# design.net
KiCad netlist of a schematic drawn in Altium Designer
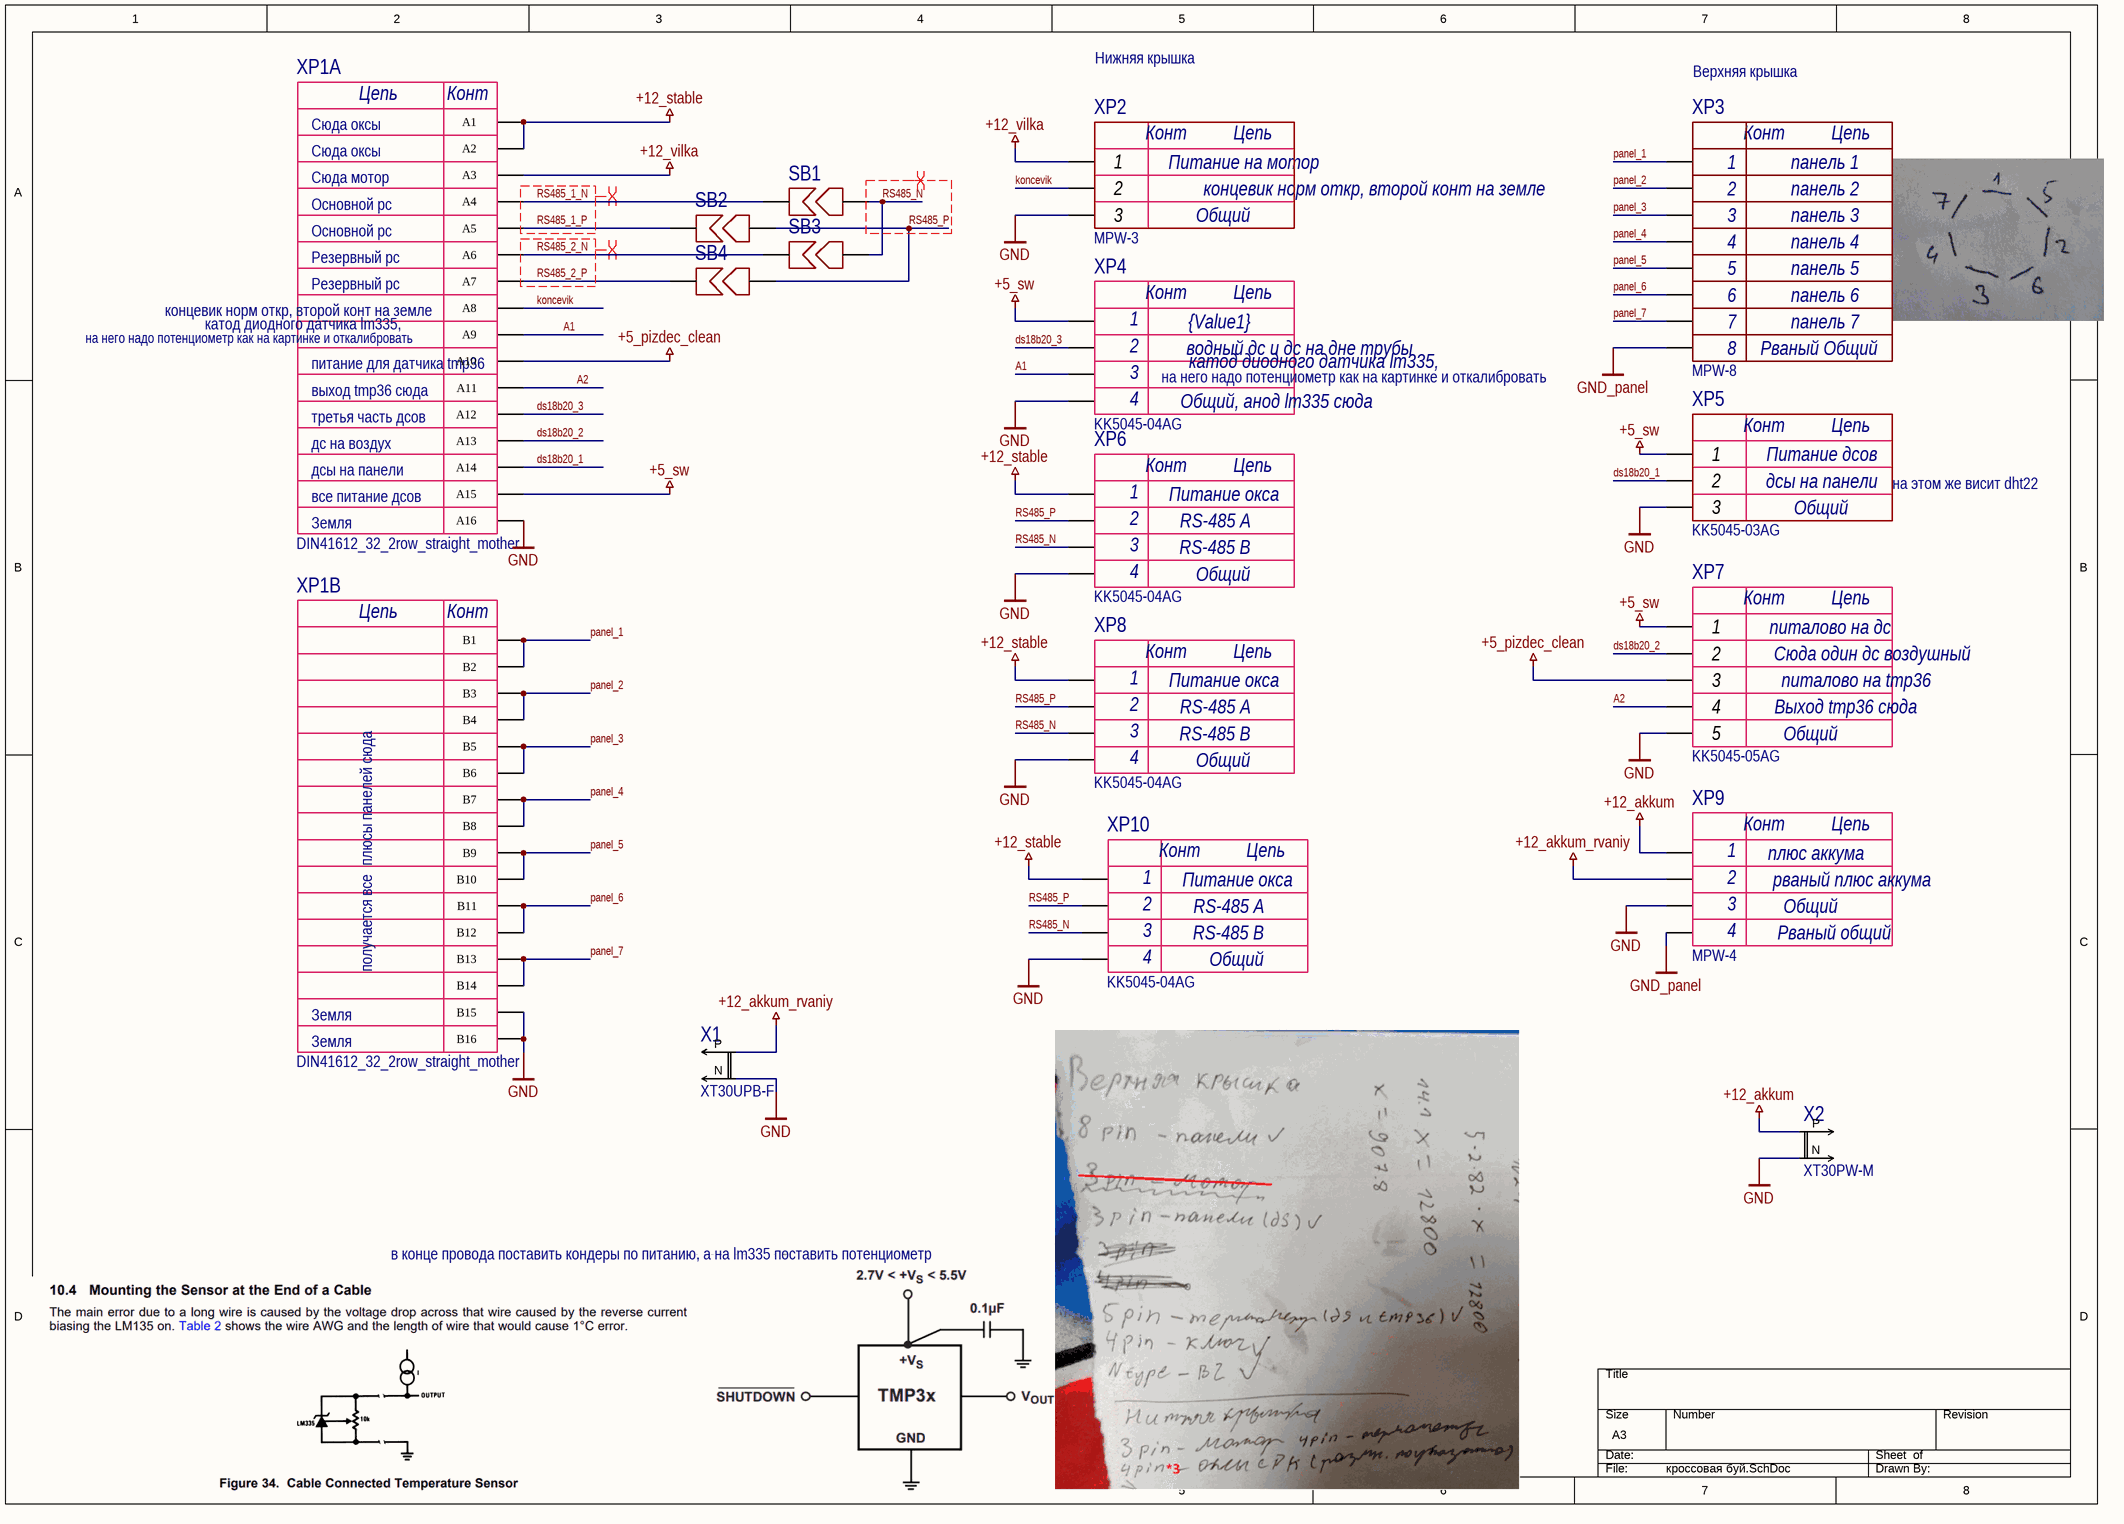
[diagram p0: кроссовая буй.SchDoc]

(export (version "E")
  (design (tool "Eeschema 10.0.6"))
  (components
    (comp (ref "SB1")
      (value "SB")
      (footprint "0805SB")
      (description "Solder bridge, мост припоя, запаиваемая перемычка, net tie, jumper")
      (libsource (lib "Hydrolib") (part "SB"))
    )
    (comp (ref "SB2")
      (value "SB")
      (footprint "0805SB")
      (description "Solder bridge, мост припоя, запаиваемая перемычка, net tie, jumper")
      (libsource (lib "Hydrolib") (part "SB"))
    )
    (comp (ref "SB3")
      (value "SB")
      (footprint "0805SB")
      (description "Solder bridge, мост припоя, запаиваемая перемычка, net tie, jumper")
      (libsource (lib "Hydrolib") (part "SB"))
    )
    (comp (ref "SB4")
      (value "SB")
      (footprint "0805SB")
      (description "Solder bridge, мост припоя, запаиваемая перемычка, net tie, jumper")
      (libsource (lib "Hydrolib") (part "SB"))
    )
    (comp (ref "X1")
      (value "XT30UPB-F")
      (footprint "XT30UPB-F")
      (description "30 А (15 продолжительно), прямая мать")
      (libsource (lib "Hydrolib") (part "Polar_Conn"))
    )
    (comp (ref "X2")
      (value "XT30PW-M")
      (footprint "XT30PW-M")
      (description "30 А (15 продолжительно), 2 контакта разъем угловой отец")
      (libsource (lib "Hydrolib") (part "Polar_Conn"))
    )
    (comp (ref "XP1")
      (value "DIN41612_32_2row_straight_mother")
      (footprint "DIN41612_32_2row_straight_mother")
      (libsource (lib "Hydrolib") (part "DIN41612_32_2row"))
    )
    (comp (ref "XP2")
      (value "MPW-3")
      (footprint "MPW-3")
      (description "MPW-3 , Вилка на плату 5.08мм прямая 3pin")
      (fields
        (field (name "VALUE3") "Общий")
        (field (name "VALUE2") "концевик норм откр, второй конт на земле")
        (field (name "VALUE1") "Питание на мотор")
      )
      (libsource (lib "Hydrolib") (part "Conn_3pin"))
    )
    (comp (ref "XP3")
      (value "MPW-8")
      (footprint "MPW-8")
      (description "MPW-8 , Вилка на плату 5.08мм прямая 8pin")
      (fields
        (field (name "VALUE1") "панель 1")
        (field (name "VALUE2") "панель 2")
        (field (name "VALUE3") "панель 3")
        (field (name "VALUE4") "панель 4")
        (field (name "VALUE5") "панель 5")
        (field (name "VALUE6") "панель 6")
        (field (name "VALUE7") "панель 7")
        (field (name "VALUE8") "Рваный Общий")
      )
      (libsource (lib "Hydrolib") (part "Conn_8pin"))
    )
    (comp (ref "XP4")
      (value "KK5045-04AG")
      (footprint "KK5045-04AG")
      (description "Разъем типа провод-плата, 2.5 мм, 4 контакта")
      (fields
        (field (name "VALUE3") "катод диодного датчика lm335,")
        (field (name "VALUE2") "водный дс и дс на дне трубы")
        (field (name "VALUE4") "Общий, анод lm335 сюда")
        (field (name "ПИТАЛОВО НА ДС") "{Value1}")
      )
      (libsource (lib "Hydrolib") (part "Conn_4pin"))
    )
    (comp (ref "XP5")
      (value "KK5045-03AG")
      (footprint "KK5045-03AG")
      (description "Разъем типа провод-плата, 2.5 мм, 3 контакта")
      (fields
        (field (name "VALUE3") "Общий")
        (field (name "VALUE2") "дсы на панели")
        (field (name "VALUE1") "Питание дсов")
      )
      (libsource (lib "Hydrolib") (part "Conn_3pin"))
    )
    (comp (ref "XP6")
      (value "KK5045-04AG")
      (footprint "KK5045-04AG")
      (description "Разъем типа провод-плата, 2.5 мм, 4 контакта")
      (fields
        (field (name "VALUE3") "RS-485 B")
        (field (name "VALUE2") "RS-485 A")
        (field (name "VALUE4") "Общий")
        (field (name "VALUE1") "Питание окса")
      )
      (libsource (lib "Hydrolib") (part "Conn_4pin"))
    )
    (comp (ref "XP7")
      (value "KK5045-05AG")
      (footprint "KK5045-05AG")
      (description "Разъем типа провод-плата, 2.5 мм, 5 контакта")
      (fields
        (field (name "VALUE1") "питалово на дс")
        (field (name "VALUE2") "Сюда один дс воздушный")
        (field (name "VALUE3") "питалово на tmp36")
        (field (name "VALUE4") "Выход tmp36 сюда")
        (field (name "VALUE5") "Общий")
      )
      (libsource (lib "Hydrolib") (part "Conn_5pin"))
    )
    (comp (ref "XP8")
      (value "KK5045-04AG")
      (footprint "KK5045-04AG")
      (description "Разъем типа провод-плата, 2.5 мм, 4 контакта")
      (fields
        (field (name "VALUE3") "RS-485 B")
        (field (name "VALUE2") "RS-485 A")
        (field (name "VALUE4") "Общий")
        (field (name "VALUE1") "Питание окса")
      )
      (libsource (lib "Hydrolib") (part "Conn_4pin"))
    )
    (comp (ref "XP9")
      (value "MPW-4")
      (footprint "MPW-4")
      (description "MPW-4 , Вилка на плату 5.08мм прямая 4pin")
      (fields
        (field (name "VALUE3") "Общий")
        (field (name "VALUE2") "рваный плюс аккума")
        (field (name "VALUE4") "Рваный общий")
        (field (name "VALUE1") "плюс аккума")
      )
      (libsource (lib "Hydrolib") (part "Conn_4pin"))
    )
    (comp (ref "XP10")
      (value "KK5045-04AG")
      (footprint "KK5045-04AG")
      (description "Разъем типа провод-плата, 2.5 мм, 4 контакта")
      (fields
        (field (name "VALUE3") "RS-485 B")
        (field (name "VALUE2") "RS-485 A")
        (field (name "VALUE4") "Общий")
        (field (name "VALUE1") "Питание окса")
      )
      (libsource (lib "Hydrolib") (part "Conn_4pin"))
    )
  )
  (nets
    (net (code "1") (name "+5_pizdec_clean") (class "Default")
      (node (ref "XP1") (pin "A10") (pinfunction "A10_A10") (pintype "passive"))
      (node (ref "XP7") (pin "3") (pinfunction "3_3") (pintype "passive"))
    )
    (net (code "2") (name "+5_sw") (class "Default")
      (node (ref "XP1") (pin "A15") (pinfunction "A15_A15") (pintype "passive"))
      (node (ref "XP4") (pin "1") (pinfunction "1_1") (pintype "passive"))
      (node (ref "XP5") (pin "1") (pinfunction "1_1") (pintype "passive"))
      (node (ref "XP7") (pin "1") (pinfunction "1_1") (pintype "passive"))
    )
    (net (code "3") (name "+12_akkum") (class "Default")
      (node (ref "X2") (pin "P") (pinfunction "P_P") (pintype "passive"))
      (node (ref "XP9") (pin "1") (pinfunction "1_1") (pintype "passive"))
    )
    (net (code "4") (name "+12_akkum_rvaniy") (class "Default")
      (node (ref "X1") (pin "P") (pinfunction "P_P") (pintype "passive"))
      (node (ref "XP9") (pin "2") (pinfunction "2_2") (pintype "passive"))
    )
    (net (code "5") (name "+12_stable") (class "Default")
      (node (ref "XP1") (pin "A1") (pinfunction "A1_A1") (pintype "passive"))
      (node (ref "XP1") (pin "A2") (pinfunction "A2_A2") (pintype "passive"))
      (node (ref "XP10") (pin "1") (pinfunction "1_1") (pintype "passive"))
      (node (ref "XP6") (pin "1") (pinfunction "1_1") (pintype "passive"))
      (node (ref "XP8") (pin "1") (pinfunction "1_1") (pintype "passive"))
    )
    (net (code "6") (name "+12_vilka") (class "Default")
      (node (ref "XP1") (pin "A3") (pinfunction "A3_A3") (pintype "passive"))
      (node (ref "XP2") (pin "1") (pinfunction "1_1") (pintype "passive"))
    )
    (net (code "7") (name "/A1") (class "Default")
      (node (ref "XP1") (pin "A9") (pinfunction "A9_A9") (pintype "passive"))
      (node (ref "XP4") (pin "3") (pinfunction "3_3") (pintype "passive"))
    )
    (net (code "8") (name "/A2") (class "Default")
      (node (ref "XP1") (pin "A11") (pinfunction "A11_A11") (pintype "passive"))
      (node (ref "XP7") (pin "4") (pinfunction "4_4") (pintype "passive"))
    )
    (net (code "9") (name "/RS485_1_N") (class "Default")
      (node (ref "SB1") (pin "1") (pinfunction "1_1") (pintype "passive"))
      (node (ref "XP1") (pin "A4") (pinfunction "A4_A4") (pintype "passive"))
    )
    (net (code "10") (name "/RS485_1_P") (class "Default")
      (node (ref "SB2") (pin "1") (pinfunction "1_1") (pintype "passive"))
      (node (ref "XP1") (pin "A5") (pinfunction "A5_A5") (pintype "passive"))
    )
    (net (code "11") (name "/RS485_2_N") (class "Default")
      (node (ref "SB3") (pin "1") (pinfunction "1_1") (pintype "passive"))
      (node (ref "XP1") (pin "A6") (pinfunction "A6_A6") (pintype "passive"))
    )
    (net (code "12") (name "/RS485_2_P") (class "Default")
      (node (ref "SB4") (pin "1") (pinfunction "1_1") (pintype "passive"))
      (node (ref "XP1") (pin "A7") (pinfunction "A7_A7") (pintype "passive"))
    )
    (net (code "13") (name "/RS485_N") (class "Default")
      (node (ref "SB1") (pin "2") (pinfunction "2_2") (pintype "passive"))
      (node (ref "SB3") (pin "2") (pinfunction "2_2") (pintype "passive"))
      (node (ref "XP10") (pin "3") (pinfunction "3_3") (pintype "passive"))
      (node (ref "XP6") (pin "3") (pinfunction "3_3") (pintype "passive"))
      (node (ref "XP8") (pin "3") (pinfunction "3_3") (pintype "passive"))
    )
    (net (code "14") (name "/RS485_P") (class "Default")
      (node (ref "SB2") (pin "2") (pinfunction "2_2") (pintype "passive"))
      (node (ref "SB4") (pin "2") (pinfunction "2_2") (pintype "passive"))
      (node (ref "XP10") (pin "2") (pinfunction "2_2") (pintype "passive"))
      (node (ref "XP6") (pin "2") (pinfunction "2_2") (pintype "passive"))
      (node (ref "XP8") (pin "2") (pinfunction "2_2") (pintype "passive"))
    )
    (net (code "15") (name "/ds18b20_1") (class "Default")
      (node (ref "XP1") (pin "A14") (pinfunction "A14_A14") (pintype "passive"))
      (node (ref "XP5") (pin "2") (pinfunction "2_2") (pintype "passive"))
    )
    (net (code "16") (name "/ds18b20_2") (class "Default")
      (node (ref "XP1") (pin "A13") (pinfunction "A13_A13") (pintype "passive"))
      (node (ref "XP7") (pin "2") (pinfunction "2_2") (pintype "passive"))
    )
    (net (code "17") (name "/ds18b20_3") (class "Default")
      (node (ref "XP1") (pin "A12") (pinfunction "A12_A12") (pintype "passive"))
      (node (ref "XP4") (pin "2") (pinfunction "2_2") (pintype "passive"))
    )
    (net (code "18") (name "/koncevik") (class "Default")
      (node (ref "XP1") (pin "A8") (pinfunction "A8_A8") (pintype "passive"))
      (node (ref "XP2") (pin "2") (pinfunction "2_2") (pintype "passive"))
    )
    (net (code "19") (name "/panel_1") (class "Default")
      (node (ref "XP1") (pin "B1") (pinfunction "B1_B1") (pintype "passive"))
      (node (ref "XP1") (pin "B2") (pinfunction "B2_B2") (pintype "passive"))
      (node (ref "XP3") (pin "1") (pinfunction "1_1") (pintype "passive"))
    )
    (net (code "20") (name "/panel_2") (class "Default")
      (node (ref "XP1") (pin "B3") (pinfunction "B3_B3") (pintype "passive"))
      (node (ref "XP1") (pin "B4") (pinfunction "B4_B4") (pintype "passive"))
      (node (ref "XP3") (pin "2") (pinfunction "2_2") (pintype "passive"))
    )
    (net (code "21") (name "/panel_3") (class "Default")
      (node (ref "XP1") (pin "B5") (pinfunction "B5_B5") (pintype "passive"))
      (node (ref "XP1") (pin "B6") (pinfunction "B6_B6") (pintype "passive"))
      (node (ref "XP3") (pin "3") (pinfunction "3_3") (pintype "passive"))
    )
    (net (code "22") (name "/panel_4") (class "Default")
      (node (ref "XP1") (pin "B7") (pinfunction "B7_B7") (pintype "passive"))
      (node (ref "XP1") (pin "B8") (pinfunction "B8_B8") (pintype "passive"))
      (node (ref "XP3") (pin "4") (pinfunction "4_4") (pintype "passive"))
    )
    (net (code "23") (name "/panel_5") (class "Default")
      (node (ref "XP1") (pin "B10") (pinfunction "B10_B10") (pintype "passive"))
      (node (ref "XP1") (pin "B9") (pinfunction "B9_B9") (pintype "passive"))
      (node (ref "XP3") (pin "5") (pinfunction "5_5") (pintype "passive"))
    )
    (net (code "24") (name "/panel_6") (class "Default")
      (node (ref "XP1") (pin "B11") (pinfunction "B11_B11") (pintype "passive"))
      (node (ref "XP1") (pin "B12") (pinfunction "B12_B12") (pintype "passive"))
      (node (ref "XP3") (pin "6") (pinfunction "6_6") (pintype "passive"))
    )
    (net (code "25") (name "/panel_7") (class "Default")
      (node (ref "XP1") (pin "B13") (pinfunction "B13_B13") (pintype "passive"))
      (node (ref "XP1") (pin "B14") (pinfunction "B14_B14") (pintype "passive"))
      (node (ref "XP3") (pin "7") (pinfunction "7_7") (pintype "passive"))
    )
    (net (code "26") (name "GND") (class "Default")
      (node (ref "X1") (pin "N") (pinfunction "N_N") (pintype "passive"))
      (node (ref "X2") (pin "N") (pinfunction "N_N") (pintype "passive"))
      (node (ref "XP1") (pin "A16") (pinfunction "A16_A16") (pintype "passive"))
      (node (ref "XP1") (pin "B15") (pinfunction "B15_B15") (pintype "passive"))
      (node (ref "XP1") (pin "B16") (pinfunction "B16_B16") (pintype "passive"))
      (node (ref "XP10") (pin "4") (pinfunction "4_4") (pintype "passive"))
      (node (ref "XP2") (pin "3") (pinfunction "3_3") (pintype "passive"))
      (node (ref "XP4") (pin "4") (pinfunction "4_4") (pintype "passive"))
      (node (ref "XP5") (pin "3") (pinfunction "3_3") (pintype "passive"))
      (node (ref "XP6") (pin "4") (pinfunction "4_4") (pintype "passive"))
      (node (ref "XP7") (pin "5") (pinfunction "5_5") (pintype "passive"))
      (node (ref "XP8") (pin "4") (pinfunction "4_4") (pintype "passive"))
      (node (ref "XP9") (pin "3") (pinfunction "3_3") (pintype "passive"))
    )
    (net (code "27") (name "GND_panel") (class "Default")
      (node (ref "XP3") (pin "8") (pinfunction "8_8") (pintype "passive"))
      (node (ref "XP9") (pin "4") (pinfunction "4_4") (pintype "passive"))
    )
  )
)
